# Sheet1.net
KiCad netlist of a schematic drawn in Altium Designer
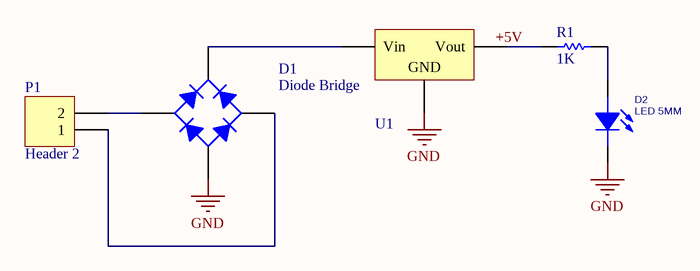
[diagram p0: Sheet1.SchDoc]

(export (version "E")
  (design (tool "Eeschema 10.0.6"))
  (components
    (comp (ref "D1")
      (value "Diode Bridge")
      (footprint "Bridge KBP PACKAGE")
      (description "Full Wave Diode Bridge")
      (fields (field (name "DESIGNER") "Abbas Basereh"))
      (libsource (lib "Altium") (part "Diode Bridge TOTAL SIZE"))
    )
    (comp (ref "D2")
      (value "LED 5MM")
      (footprint "LED5MM_BLUE")
      (description "Light Emitting Diode")
      (fields (field (name "DESIGNER") "Abbas Basereh"))
      (libsource (lib "Altium") (part "LED 5MM"))
    )
    (comp (ref "P1")
      (value "Header 2")
      (footprint "HDR1X2")
      (description "Header, 2-Pin")
      (fields (field (name "PUBLISHER") "Altium Limited"))
      (libsource (lib "Altium") (part "Header 2"))
    )
    (comp (ref "R1")
      (value "1K")
      (footprint "Axial 0_25 W, 0_4 IN LEAD PITCH")
      (description "RES Axial 0.25W")
      (fields (field (name "DESIGNER") "Abbas Basereh"))
      (libsource (lib "Altium") (part "RES Axial 0.25W"))
    )
    (comp (ref "U1")
      (value "L7805CV")
      (footprint "TO-220 AB")
      (description "Linear Voltage Regulator IC Positive FIXED")
      (fields (field (name "MANUFACTURER") "STMicroelectronics") (field (name "DESIGNER") "Abbas Basereh"))
      (libsource (lib "Altium") (part "L7805CV-Linear Voltage Regulator IC Positive 1 Output 5V 1.5A TO-220AB"))
    )
  )
  (nets
    (net (code "1") (name "/+5V") (class "Default")
      (node (ref "R1") (pin "2") (pinfunction "2_2") (pintype "passive"))
      (node (ref "U1") (pin "3") (pinfunction "Vout_3") (pintype "passive"))
    )
    (net (code "2") (name "GND") (class "Default")
      (node (ref "D1") (pin "4") (pinfunction "-_4") (pintype "passive"))
      (node (ref "D2") (pin "2") (pinfunction "CATHODE_2") (pintype "passive"))
      (node (ref "U1") (pin "2") (pinfunction "GND_2") (pintype "passive"))
    )
    (net (code "3") (name "Net-(D1-+)") (class "Default")
      (node (ref "D1") (pin "1") (pinfunction "+_1") (pintype "passive"))
      (node (ref "U1") (pin "1") (pinfunction "Vin_1") (pintype "passive"))
    )
    (net (code "4") (name "Net-(D1-AC-Pad2)") (class "Default")
      (node (ref "D1") (pin "2") (pinfunction "AC_2") (pintype "passive"))
      (node (ref "P1") (pin "2") (pinfunction "2_2") (pintype "passive"))
    )
    (net (code "5") (name "Net-(D1-AC-Pad3)") (class "Default")
      (node (ref "D1") (pin "3") (pinfunction "AC_3") (pintype "passive"))
      (node (ref "P1") (pin "1") (pinfunction "1_1") (pintype "passive"))
    )
    (net (code "6") (name "Net-(D2-ANODE)") (class "Default")
      (node (ref "D2") (pin "1") (pinfunction "ANODE_1") (pintype "passive"))
      (node (ref "R1") (pin "1") (pinfunction "1_1") (pintype "passive"))
    )
  )
)
